# RPi-DPI-HAT_v10.net
KiCad netlist of a schematic drawn in EAGLE
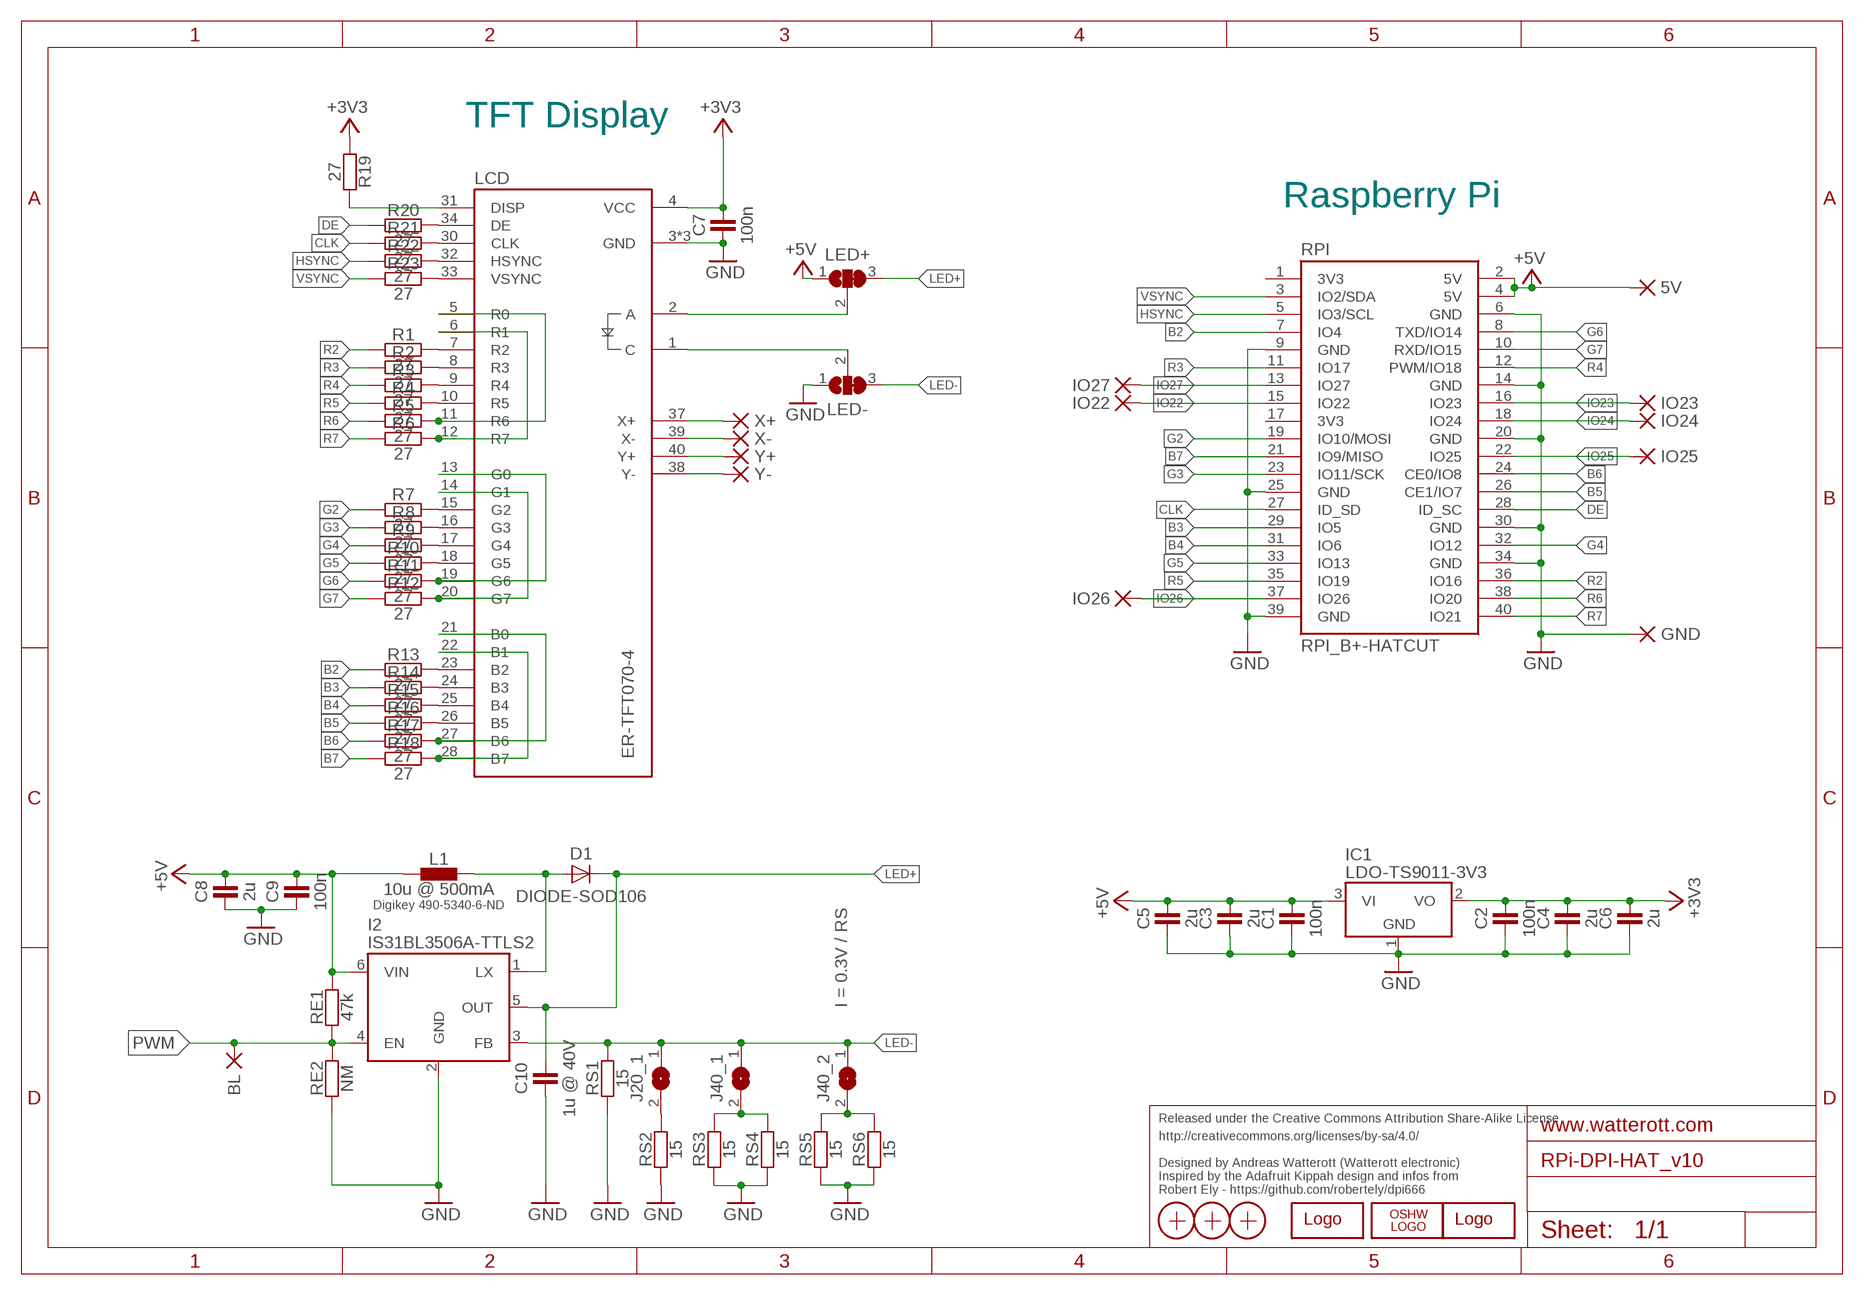
[diagram p0: schematic, sheet 1]

(export (version "E")
  (design (tool "Eeschema 10.0.6"))
  (components
    (comp (ref "5V")
      (value "PAD-0.80X1.60_NC")
      (footprint "eagle-import:PAD-0.80X1.60_NC")
      (libsource (lib "eagle-import") (part "PAD-0.80X1.60_NC"))
    )
    (comp (ref "BL")
      (value "PAD-0.80X1.60_NC")
      (footprint "eagle-import:PAD-0.80X1.60_NC")
      (libsource (lib "eagle-import") (part "PAD-0.80X1.60_NC"))
    )
    (comp (ref "C1")
      (value "100n")
      (footprint "eagle-import:C0402")
      (libsource (lib "eagle-import") (part "CAPACITOR-0402"))
    )
    (comp (ref "C2")
      (value "100n")
      (footprint "eagle-import:C0402")
      (libsource (lib "eagle-import") (part "CAPACITOR-0402"))
    )
    (comp (ref "C3")
      (value "2u")
      (footprint "eagle-import:C0402")
      (libsource (lib "eagle-import") (part "CAPACITOR-0402"))
    )
    (comp (ref "C4")
      (value "2u")
      (footprint "eagle-import:C0402")
      (libsource (lib "eagle-import") (part "CAPACITOR-0402"))
    )
    (comp (ref "C5")
      (value "2u")
      (footprint "eagle-import:C0402")
      (libsource (lib "eagle-import") (part "CAPACITOR-0402"))
    )
    (comp (ref "C6")
      (value "2u")
      (footprint "eagle-import:C0402")
      (libsource (lib "eagle-import") (part "CAPACITOR-0402"))
    )
    (comp (ref "C7")
      (value "100n")
      (footprint "eagle-import:C0402")
      (libsource (lib "eagle-import") (part "CAPACITOR-0402"))
    )
    (comp (ref "C8")
      (value "2u")
      (footprint "eagle-import:C0402")
      (libsource (lib "eagle-import") (part "CAPACITOR-0402"))
    )
    (comp (ref "C9")
      (value "100n")
      (footprint "eagle-import:C0402")
      (libsource (lib "eagle-import") (part "CAPACITOR-0402"))
    )
    (comp (ref "C10")
      (value "1u @ 40V")
      (footprint "eagle-import:C0805")
      (libsource (lib "eagle-import") (part "CAPACITOR-0805"))
    )
    (comp (ref "D1")
      (value "DIODE-SOD106")
      (footprint "eagle-import:SOD106")
      (libsource (lib "eagle-import") (part "DIODE-SOD106"))
    )
    (comp (ref "GND")
      (value "PAD-0.80X1.60_NC")
      (footprint "eagle-import:PAD-0.80X1.60_NC")
      (libsource (lib "eagle-import") (part "PAD-0.80X1.60_NC"))
    )
    (comp (ref "I2")
      (value "IS31BL3506A-TTLS2")
      (footprint "eagle-import:SOT23-6")
      (libsource (lib "eagle-import") (part "IS31BL3506A-TTLS2"))
    )
    (comp (ref "IC1")
      (value "LDO-TS9011-3V3")
      (footprint "eagle-import:SOT23")
      (libsource (lib "eagle-import") (part "LDO-TS9011-3V3"))
    )
    (comp (ref "IO22")
      (value "PAD-0.80X1.60_NC")
      (footprint "eagle-import:PAD-0.80X1.60_NC")
      (libsource (lib "eagle-import") (part "PAD-0.80X1.60_NC"))
    )
    (comp (ref "IO23")
      (value "PAD-0.80X1.60_NC")
      (footprint "eagle-import:PAD-0.80X1.60_NC")
      (libsource (lib "eagle-import") (part "PAD-0.80X1.60_NC"))
    )
    (comp (ref "IO24")
      (value "PAD-0.80X1.60_NC")
      (footprint "eagle-import:PAD-0.80X1.60_NC")
      (libsource (lib "eagle-import") (part "PAD-0.80X1.60_NC"))
    )
    (comp (ref "IO25")
      (value "PAD-0.80X1.60_NC")
      (footprint "eagle-import:PAD-0.80X1.60_NC")
      (libsource (lib "eagle-import") (part "PAD-0.80X1.60_NC"))
    )
    (comp (ref "IO26")
      (value "PAD-0.80X1.60_NC")
      (footprint "eagle-import:PAD-0.80X1.60_NC")
      (libsource (lib "eagle-import") (part "PAD-0.80X1.60_NC"))
    )
    (comp (ref "IO27")
      (value "PAD-0.80X1.60_NC")
      (footprint "eagle-import:PAD-0.80X1.60_NC")
      (libsource (lib "eagle-import") (part "PAD-0.80X1.60_NC"))
    )
    (comp (ref "J20_1")
      (value "JUMPER2-0402")
      (footprint "eagle-import:JUMPER2-0402")
      (libsource (lib "eagle-import") (part "JUMPER2-0402"))
    )
    (comp (ref "J40_1")
      (value "JUMPER2-0402")
      (footprint "eagle-import:JUMPER2-0402")
      (libsource (lib "eagle-import") (part "JUMPER2-0402"))
    )
    (comp (ref "J40_2")
      (value "JUMPER2-0402")
      (footprint "eagle-import:JUMPER2-0402")
      (libsource (lib "eagle-import") (part "JUMPER2-0402"))
    )
    (comp (ref "L1")
      (value "10u @ 500mA")
      (footprint "eagle-import:L_1212")
      (libsource (lib "eagle-import") (part "INDUCTOR-1212"))
    )
    (comp (ref "LCD")
      (value "ER-TFT070-4")
      (footprint "eagle-import:FPC40")
      (libsource (lib "eagle-import") (part "ER-TFT070-4"))
    )
    (comp (ref "LED+")
      (value "JUMPER3-0603-NC")
      (footprint "eagle-import:JUMPER3-0603_NC")
      (libsource (lib "eagle-import") (part "JUMPER3-0603-NC"))
    )
    (comp (ref "LED-")
      (value "JUMPER3-0603-NC")
      (footprint "eagle-import:JUMPER3-0603_NC")
      (libsource (lib "eagle-import") (part "JUMPER3-0603-NC"))
    )
    (comp (ref "LOGO1")
      (value "LOGO-S_PLACE_S")
      (footprint "eagle-import:SPARK_TPLACE_S")
      (libsource (lib "eagle-import") (part "LOGO-S_PLACE_S"))
    )
    (comp (ref "LOGO2")
      (value "OSHW_LOGOX0070")
      (footprint "eagle-import:OSHW_6X70")
      (libsource (lib "eagle-import") (part "OSHW_LOGOX0070"))
    )
    (comp (ref "LOGO3")
      (value "LOGO-PLACE")
      (footprint "eagle-import:LOGO_TPLACE")
      (libsource (lib "eagle-import") (part "LOGO-PLACE"))
    )
    (comp (ref "R1")
      (value "27")
      (footprint "eagle-import:C0402")
      (libsource (lib "eagle-import") (part "RESISTOR-0402"))
    )
    (comp (ref "R2")
      (value "27")
      (footprint "eagle-import:C0402")
      (libsource (lib "eagle-import") (part "RESISTOR-0402"))
    )
    (comp (ref "R3")
      (value "27")
      (footprint "eagle-import:C0402")
      (libsource (lib "eagle-import") (part "RESISTOR-0402"))
    )
    (comp (ref "R4")
      (value "27")
      (footprint "eagle-import:C0402")
      (libsource (lib "eagle-import") (part "RESISTOR-0402"))
    )
    (comp (ref "R5")
      (value "27")
      (footprint "eagle-import:C0402")
      (libsource (lib "eagle-import") (part "RESISTOR-0402"))
    )
    (comp (ref "R6")
      (value "27")
      (footprint "eagle-import:C0402")
      (libsource (lib "eagle-import") (part "RESISTOR-0402"))
    )
    (comp (ref "R7")
      (value "27")
      (footprint "eagle-import:C0402")
      (libsource (lib "eagle-import") (part "RESISTOR-0402"))
    )
    (comp (ref "R8")
      (value "27")
      (footprint "eagle-import:C0402")
      (libsource (lib "eagle-import") (part "RESISTOR-0402"))
    )
    (comp (ref "R9")
      (value "27")
      (footprint "eagle-import:C0402")
      (libsource (lib "eagle-import") (part "RESISTOR-0402"))
    )
    (comp (ref "R10")
      (value "27")
      (footprint "eagle-import:C0402")
      (libsource (lib "eagle-import") (part "RESISTOR-0402"))
    )
    (comp (ref "R11")
      (value "27")
      (footprint "eagle-import:C0402")
      (libsource (lib "eagle-import") (part "RESISTOR-0402"))
    )
    (comp (ref "R12")
      (value "27")
      (footprint "eagle-import:C0402")
      (libsource (lib "eagle-import") (part "RESISTOR-0402"))
    )
    (comp (ref "R13")
      (value "27")
      (footprint "eagle-import:C0402")
      (libsource (lib "eagle-import") (part "RESISTOR-0402"))
    )
    (comp (ref "R14")
      (value "27")
      (footprint "eagle-import:C0402")
      (libsource (lib "eagle-import") (part "RESISTOR-0402"))
    )
    (comp (ref "R15")
      (value "27")
      (footprint "eagle-import:C0402")
      (libsource (lib "eagle-import") (part "RESISTOR-0402"))
    )
    (comp (ref "R16")
      (value "27")
      (footprint "eagle-import:C0402")
      (libsource (lib "eagle-import") (part "RESISTOR-0402"))
    )
    (comp (ref "R17")
      (value "27")
      (footprint "eagle-import:C0402")
      (libsource (lib "eagle-import") (part "RESISTOR-0402"))
    )
    (comp (ref "R18")
      (value "27")
      (footprint "eagle-import:C0402")
      (libsource (lib "eagle-import") (part "RESISTOR-0402"))
    )
    (comp (ref "R19")
      (value "27")
      (footprint "eagle-import:C0402")
      (libsource (lib "eagle-import") (part "RESISTOR-0402"))
    )
    (comp (ref "R20")
      (value "27")
      (footprint "eagle-import:C0402")
      (libsource (lib "eagle-import") (part "RESISTOR-0402"))
    )
    (comp (ref "R21")
      (value "27")
      (footprint "eagle-import:C0402")
      (libsource (lib "eagle-import") (part "RESISTOR-0402"))
    )
    (comp (ref "R22")
      (value "27")
      (footprint "eagle-import:C0402")
      (libsource (lib "eagle-import") (part "RESISTOR-0402"))
    )
    (comp (ref "R23")
      (value "27")
      (footprint "eagle-import:C0402")
      (libsource (lib "eagle-import") (part "RESISTOR-0402"))
    )
    (comp (ref "RE1")
      (value "47k")
      (footprint "eagle-import:C0402")
      (libsource (lib "eagle-import") (part "RESISTOR-0402"))
    )
    (comp (ref "RE2")
      (value "NM")
      (footprint "eagle-import:C0402")
      (libsource (lib "eagle-import") (part "RESISTOR-0402"))
    )
    (comp (ref "RPI")
      (value "RPI_B+-HATCUT")
      (footprint "eagle-import:RPI-B+HAT_CUTOUT")
      (libsource (lib "eagle-import") (part "RPI_B+-HATCUT"))
    )
    (comp (ref "RS1")
      (value "15")
      (footprint "eagle-import:C0402")
      (libsource (lib "eagle-import") (part "RESISTOR-0402"))
    )
    (comp (ref "RS2")
      (value "15")
      (footprint "eagle-import:C0402")
      (libsource (lib "eagle-import") (part "RESISTOR-0402"))
    )
    (comp (ref "RS3")
      (value "15")
      (footprint "eagle-import:C0402")
      (libsource (lib "eagle-import") (part "RESISTOR-0402"))
    )
    (comp (ref "RS4")
      (value "15")
      (footprint "eagle-import:C0402")
      (libsource (lib "eagle-import") (part "RESISTOR-0402"))
    )
    (comp (ref "RS5")
      (value "15")
      (footprint "eagle-import:C0402")
      (libsource (lib "eagle-import") (part "RESISTOR-0402"))
    )
    (comp (ref "RS6")
      (value "15")
      (footprint "eagle-import:C0402")
      (libsource (lib "eagle-import") (part "RESISTOR-0402"))
    )
    (comp (ref "X+")
      (value "PAD-0.80X1.60_NC")
      (footprint "eagle-import:PAD-0.80X1.60_NC")
      (libsource (lib "eagle-import") (part "PAD-0.80X1.60_NC"))
    )
    (comp (ref "X-")
      (value "PAD-0.80X1.60_NC")
      (footprint "eagle-import:PAD-0.80X1.60_NC")
      (libsource (lib "eagle-import") (part "PAD-0.80X1.60_NC"))
    )
    (comp (ref "X1")
      (value "PASSER-07")
      (footprint "eagle-import:PASSER_07MM")
      (libsource (lib "eagle-import") (part "PASSER-07"))
    )
    (comp (ref "X2")
      (value "PASSER-07")
      (footprint "eagle-import:PASSER_07MM")
      (libsource (lib "eagle-import") (part "PASSER-07"))
    )
    (comp (ref "X3")
      (value "PASSER-07")
      (footprint "eagle-import:PASSER_07MM")
      (libsource (lib "eagle-import") (part "PASSER-07"))
    )
    (comp (ref "Y+")
      (value "PAD-0.80X1.60_NC")
      (footprint "eagle-import:PAD-0.80X1.60_NC")
      (libsource (lib "eagle-import") (part "PAD-0.80X1.60_NC"))
    )
    (comp (ref "Y-")
      (value "PAD-0.80X1.60_NC")
      (footprint "eagle-import:PAD-0.80X1.60_NC")
      (libsource (lib "eagle-import") (part "PAD-0.80X1.60_NC"))
    )
  )
  (nets
    (net (code "1") (name "+3V3") (class "Default")
      (node (ref "C2") (pin "2") (pinfunction "2_2") (pintype "passive"))
      (node (ref "C4") (pin "2") (pinfunction "2_2") (pintype "passive"))
      (node (ref "C6") (pin "2") (pinfunction "2_2") (pintype "passive"))
      (node (ref "C7") (pin "2") (pinfunction "2_2") (pintype "passive"))
      (node (ref "IC1") (pin "2") (pinfunction "VO_2") (pintype "passive"))
      (node (ref "LCD") (pin "4") (pinfunction "VCC_4") (pintype "power_in"))
      (node (ref "R19") (pin "1") (pinfunction "1_1") (pintype "passive"))
    )
    (net (code "2") (name "+5V") (class "Default")
      (node (ref "5V") (pin "1") (pinfunction "P_1") (pintype "passive"))
      (node (ref "C1") (pin "2") (pinfunction "2_2") (pintype "passive"))
      (node (ref "C3") (pin "2") (pinfunction "2_2") (pintype "passive"))
      (node (ref "C5") (pin "2") (pinfunction "2_2") (pintype "passive"))
      (node (ref "C8") (pin "2") (pinfunction "2_2") (pintype "passive"))
      (node (ref "C9") (pin "2") (pinfunction "2_2") (pintype "passive"))
      (node (ref "I2") (pin "6") (pinfunction "VIN_6") (pintype "power_in"))
      (node (ref "IC1") (pin "3") (pinfunction "VI_3") (pintype "input"))
      (node (ref "L1") (pin "1") (pinfunction "1_1") (pintype "passive"))
      (node (ref "LED+") (pin "1") (pinfunction "1_1") (pintype "passive"))
      (node (ref "RE1") (pin "2") (pinfunction "2_2") (pintype "passive"))
      (node (ref "RPI") (pin "2") (pinfunction "5V_2") (pintype "passive"))
      (node (ref "RPI") (pin "4") (pinfunction "5V_4") (pintype "passive"))
    )
    (net (code "3") (name "B2") (class "Default")
      (node (ref "R13") (pin "1") (pinfunction "1_1") (pintype "passive"))
      (node (ref "RPI") (pin "7") (pinfunction "IO4_7") (pintype "passive"))
    )
    (net (code "4") (name "B3") (class "Default")
      (node (ref "R14") (pin "1") (pinfunction "1_1") (pintype "passive"))
      (node (ref "RPI") (pin "29") (pinfunction "IO5_29") (pintype "bidirectional"))
    )
    (net (code "5") (name "B4") (class "Default")
      (node (ref "R15") (pin "1") (pinfunction "1_1") (pintype "passive"))
      (node (ref "RPI") (pin "31") (pinfunction "IO6_31") (pintype "bidirectional"))
    )
    (net (code "6") (name "B5") (class "Default")
      (node (ref "R16") (pin "1") (pinfunction "1_1") (pintype "passive"))
      (node (ref "RPI") (pin "26") (pinfunction "CE1/IO7_26") (pintype "passive"))
    )
    (net (code "7") (name "B6") (class "Default")
      (node (ref "R17") (pin "1") (pinfunction "1_1") (pintype "passive"))
      (node (ref "RPI") (pin "24") (pinfunction "CE0/IO8_24") (pintype "passive"))
    )
    (net (code "8") (name "B7") (class "Default")
      (node (ref "R18") (pin "1") (pinfunction "1_1") (pintype "passive"))
      (node (ref "RPI") (pin "21") (pinfunction "IO9/MISO_21") (pintype "passive"))
    )
    (net (code "9") (name "CLK") (class "Default")
      (node (ref "R21") (pin "1") (pinfunction "1_1") (pintype "passive"))
      (node (ref "RPI") (pin "27") (pinfunction "ID_SD_27") (pintype "bidirectional"))
    )
    (net (code "10") (name "DE") (class "Default")
      (node (ref "R20") (pin "1") (pinfunction "1_1") (pintype "passive"))
      (node (ref "RPI") (pin "28") (pinfunction "ID_SC_28") (pintype "bidirectional"))
    )
    (net (code "11") (name "G2") (class "Default")
      (node (ref "R7") (pin "1") (pinfunction "1_1") (pintype "passive"))
      (node (ref "RPI") (pin "19") (pinfunction "IO10/MOSI_19") (pintype "passive"))
    )
    (net (code "12") (name "G3") (class "Default")
      (node (ref "R8") (pin "1") (pinfunction "1_1") (pintype "passive"))
      (node (ref "RPI") (pin "23") (pinfunction "IO11/SCK_23") (pintype "passive"))
    )
    (net (code "13") (name "G4") (class "Default")
      (node (ref "R9") (pin "1") (pinfunction "1_1") (pintype "passive"))
      (node (ref "RPI") (pin "32") (pinfunction "IO12_32") (pintype "bidirectional"))
    )
    (net (code "14") (name "G5") (class "Default")
      (node (ref "R10") (pin "1") (pinfunction "1_1") (pintype "passive"))
      (node (ref "RPI") (pin "33") (pinfunction "IO13_33") (pintype "bidirectional"))
    )
    (net (code "15") (name "G6") (class "Default")
      (node (ref "R11") (pin "1") (pinfunction "1_1") (pintype "passive"))
      (node (ref "RPI") (pin "8") (pinfunction "TXD/IO14_8") (pintype "passive"))
    )
    (net (code "16") (name "G7") (class "Default")
      (node (ref "R12") (pin "1") (pinfunction "1_1") (pintype "passive"))
      (node (ref "RPI") (pin "10") (pinfunction "RXD/IO15_10") (pintype "passive"))
    )
    (net (code "17") (name "GND") (class "Default")
      (node (ref "C1") (pin "1") (pinfunction "1_1") (pintype "passive"))
      (node (ref "C10") (pin "1") (pinfunction "1_1") (pintype "passive"))
      (node (ref "C2") (pin "1") (pinfunction "1_1") (pintype "passive"))
      (node (ref "C3") (pin "1") (pinfunction "1_1") (pintype "passive"))
      (node (ref "C4") (pin "1") (pinfunction "1_1") (pintype "passive"))
      (node (ref "C5") (pin "1") (pinfunction "1_1") (pintype "passive"))
      (node (ref "C6") (pin "1") (pinfunction "1_1") (pintype "passive"))
      (node (ref "C7") (pin "1") (pinfunction "1_1") (pintype "passive"))
      (node (ref "C8") (pin "1") (pinfunction "1_1") (pintype "passive"))
      (node (ref "C9") (pin "1") (pinfunction "1_1") (pintype "passive"))
      (node (ref "GND") (pin "1") (pinfunction "P_1") (pintype "passive"))
      (node (ref "I2") (pin "2") (pinfunction "GND_2") (pintype "power_in"))
      (node (ref "IC1") (pin "1") (pinfunction "GND_1") (pintype "passive"))
      (node (ref "LCD") (pin "29") (pinfunction "GND_29") (pintype "power_in"))
      (node (ref "LCD") (pin "3") (pinfunction "GND_3") (pintype "power_in"))
      (node (ref "LCD") (pin "36") (pinfunction "GND_36") (pintype "power_in"))
      (node (ref "LED-") (pin "1") (pinfunction "1_1") (pintype "passive"))
      (node (ref "RE2") (pin "1") (pinfunction "1_1") (pintype "passive"))
      (node (ref "RPI") (pin "14") (pinfunction "GND_14") (pintype "passive"))
      (node (ref "RPI") (pin "20") (pinfunction "GND_20") (pintype "passive"))
      (node (ref "RPI") (pin "25") (pinfunction "GND_25") (pintype "passive"))
      (node (ref "RPI") (pin "30") (pinfunction "GND_30") (pintype "bidirectional"))
      (node (ref "RPI") (pin "34") (pinfunction "GND_34") (pintype "bidirectional"))
      (node (ref "RPI") (pin "39") (pinfunction "GND_39") (pintype "bidirectional"))
      (node (ref "RPI") (pin "6") (pinfunction "GND_6") (pintype "passive"))
      (node (ref "RPI") (pin "9") (pinfunction "GND_9") (pintype "passive"))
      (node (ref "RS1") (pin "1") (pinfunction "1_1") (pintype "passive"))
      (node (ref "RS2") (pin "1") (pinfunction "1_1") (pintype "passive"))
      (node (ref "RS3") (pin "1") (pinfunction "1_1") (pintype "passive"))
      (node (ref "RS4") (pin "1") (pinfunction "1_1") (pintype "passive"))
      (node (ref "RS5") (pin "1") (pinfunction "1_1") (pintype "passive"))
      (node (ref "RS6") (pin "1") (pinfunction "1_1") (pintype "passive"))
    )
    (net (code "18") (name "HSYNC") (class "Default")
      (node (ref "R22") (pin "1") (pinfunction "1_1") (pintype "passive"))
      (node (ref "RPI") (pin "5") (pinfunction "IO3/SCL_5") (pintype "passive"))
    )
    (net (code "19") (name "IO22") (class "Default")
      (node (ref "IO22") (pin "1") (pinfunction "P_1") (pintype "passive"))
      (node (ref "RPI") (pin "15") (pinfunction "IO22_15") (pintype "passive"))
    )
    (net (code "20") (name "IO23") (class "Default")
      (node (ref "IO23") (pin "1") (pinfunction "P_1") (pintype "passive"))
      (node (ref "RPI") (pin "16") (pinfunction "IO23_16") (pintype "passive"))
    )
    (net (code "21") (name "IO24") (class "Default")
      (node (ref "IO24") (pin "1") (pinfunction "P_1") (pintype "passive"))
      (node (ref "RPI") (pin "18") (pinfunction "IO24_18") (pintype "passive"))
    )
    (net (code "22") (name "IO25") (class "Default")
      (node (ref "IO25") (pin "1") (pinfunction "P_1") (pintype "passive"))
      (node (ref "RPI") (pin "22") (pinfunction "IO25_22") (pintype "passive"))
    )
    (net (code "23") (name "IO26") (class "Default")
      (node (ref "IO26") (pin "1") (pinfunction "P_1") (pintype "passive"))
      (node (ref "RPI") (pin "37") (pinfunction "IO26_37") (pintype "bidirectional"))
    )
    (net (code "24") (name "IO27") (class "Default")
      (node (ref "IO27") (pin "1") (pinfunction "P_1") (pintype "passive"))
      (node (ref "RPI") (pin "13") (pinfunction "IO27_13") (pintype "passive"))
    )
    (net (code "25") (name "LED+") (class "Default")
      (node (ref "C10") (pin "2") (pinfunction "2_2") (pintype "passive"))
      (node (ref "D1") (pin "C") (pinfunction "C_C") (pintype "passive"))
      (node (ref "I2") (pin "5") (pinfunction "OUT_5") (pintype "power_in"))
      (node (ref "LED+") (pin "3") (pinfunction "3_3") (pintype "passive"))
    )
    (net (code "26") (name "LED-") (class "Default")
      (node (ref "I2") (pin "3") (pinfunction "FB_3") (pintype "input"))
      (node (ref "J20_1") (pin "1") (pinfunction "1_1") (pintype "passive"))
      (node (ref "J40_1") (pin "1") (pinfunction "1_1") (pintype "passive"))
      (node (ref "J40_2") (pin "1") (pinfunction "1_1") (pintype "passive"))
      (node (ref "LED-") (pin "3") (pinfunction "3_3") (pintype "passive"))
      (node (ref "RS1") (pin "2") (pinfunction "2_2") (pintype "passive"))
    )
    (net (code "27") (name "Net-(I2-LX)") (class "Default")
      (node (ref "D1") (pin "A") (pinfunction "A_A") (pintype "passive"))
      (node (ref "I2") (pin "1") (pinfunction "LX_1") (pintype "power_in"))
      (node (ref "L1") (pin "2") (pinfunction "2_2") (pintype "passive"))
    )
    (net (code "28") (name "Net-(J20_1-Pad2)") (class "Default")
      (node (ref "J20_1") (pin "2") (pinfunction "2_2") (pintype "passive"))
      (node (ref "RS2") (pin "2") (pinfunction "2_2") (pintype "passive"))
    )
    (net (code "29") (name "Net-(J40_1-Pad2)") (class "Default")
      (node (ref "J40_1") (pin "2") (pinfunction "2_2") (pintype "passive"))
      (node (ref "RS3") (pin "2") (pinfunction "2_2") (pintype "passive"))
      (node (ref "RS4") (pin "2") (pinfunction "2_2") (pintype "passive"))
    )
    (net (code "30") (name "Net-(J40_2-Pad2)") (class "Default")
      (node (ref "J40_2") (pin "2") (pinfunction "2_2") (pintype "passive"))
      (node (ref "RS5") (pin "2") (pinfunction "2_2") (pintype "passive"))
      (node (ref "RS6") (pin "2") (pinfunction "2_2") (pintype "passive"))
    )
    (net (code "31") (name "Net-(LCD-A)") (class "Default")
      (node (ref "LCD") (pin "2") (pinfunction "A_2") (pintype "power_in"))
      (node (ref "LED+") (pin "2") (pinfunction "2_2") (pintype "passive"))
    )
    (net (code "32") (name "Net-(LCD-B0)") (class "Default")
      (node (ref "LCD") (pin "21") (pinfunction "B0_21") (pintype "input"))
      (node (ref "LCD") (pin "27") (pinfunction "B6_27") (pintype "input"))
      (node (ref "R17") (pin "2") (pinfunction "2_2") (pintype "passive"))
    )
    (net (code "33") (name "Net-(LCD-B1)") (class "Default")
      (node (ref "LCD") (pin "22") (pinfunction "B1_22") (pintype "input"))
      (node (ref "LCD") (pin "28") (pinfunction "B7_28") (pintype "input"))
      (node (ref "R18") (pin "2") (pinfunction "2_2") (pintype "passive"))
    )
    (net (code "34") (name "Net-(LCD-B2)") (class "Default")
      (node (ref "LCD") (pin "23") (pinfunction "B2_23") (pintype "input"))
      (node (ref "R13") (pin "2") (pinfunction "2_2") (pintype "passive"))
    )
    (net (code "35") (name "Net-(LCD-B3)") (class "Default")
      (node (ref "LCD") (pin "24") (pinfunction "B3_24") (pintype "input"))
      (node (ref "R14") (pin "2") (pinfunction "2_2") (pintype "passive"))
    )
    (net (code "36") (name "Net-(LCD-B4)") (class "Default")
      (node (ref "LCD") (pin "25") (pinfunction "B4_25") (pintype "input"))
      (node (ref "R15") (pin "2") (pinfunction "2_2") (pintype "passive"))
    )
    (net (code "37") (name "Net-(LCD-B5)") (class "Default")
      (node (ref "LCD") (pin "26") (pinfunction "B5_26") (pintype "input"))
      (node (ref "R16") (pin "2") (pinfunction "2_2") (pintype "passive"))
    )
    (net (code "38") (name "Net-(LCD-C)") (class "Default")
      (node (ref "LCD") (pin "1") (pinfunction "C_1") (pintype "power_in"))
      (node (ref "LED-") (pin "2") (pinfunction "2_2") (pintype "passive"))
    )
    (net (code "39") (name "Net-(LCD-CLK)") (class "Default")
      (node (ref "LCD") (pin "30") (pinfunction "CLK_30") (pintype "input"))
      (node (ref "R21") (pin "2") (pinfunction "2_2") (pintype "passive"))
    )
    (net (code "40") (name "Net-(LCD-DE)") (class "Default")
      (node (ref "LCD") (pin "34") (pinfunction "DE_34") (pintype "input"))
      (node (ref "R20") (pin "2") (pinfunction "2_2") (pintype "passive"))
    )
    (net (code "41") (name "Net-(LCD-DISP)") (class "Default")
      (node (ref "LCD") (pin "31") (pinfunction "DISP_31") (pintype "input"))
      (node (ref "R19") (pin "2") (pinfunction "2_2") (pintype "passive"))
    )
    (net (code "42") (name "Net-(LCD-G0)") (class "Default")
      (node (ref "LCD") (pin "13") (pinfunction "G0_13") (pintype "input"))
      (node (ref "LCD") (pin "19") (pinfunction "G6_19") (pintype "input"))
      (node (ref "R11") (pin "2") (pinfunction "2_2") (pintype "passive"))
    )
    (net (code "43") (name "Net-(LCD-G1)") (class "Default")
      (node (ref "LCD") (pin "14") (pinfunction "G1_14") (pintype "input"))
      (node (ref "LCD") (pin "20") (pinfunction "G7_20") (pintype "input"))
      (node (ref "R12") (pin "2") (pinfunction "2_2") (pintype "passive"))
    )
    (net (code "44") (name "Net-(LCD-G2)") (class "Default")
      (node (ref "LCD") (pin "15") (pinfunction "G2_15") (pintype "input"))
      (node (ref "R7") (pin "2") (pinfunction "2_2") (pintype "passive"))
    )
    (net (code "45") (name "Net-(LCD-G3)") (class "Default")
      (node (ref "LCD") (pin "16") (pinfunction "G3_16") (pintype "input"))
      (node (ref "R8") (pin "2") (pinfunction "2_2") (pintype "passive"))
    )
    (net (code "46") (name "Net-(LCD-G4)") (class "Default")
      (node (ref "LCD") (pin "17") (pinfunction "G4_17") (pintype "input"))
      (node (ref "R9") (pin "2") (pinfunction "2_2") (pintype "passive"))
    )
    (net (code "47") (name "Net-(LCD-G5)") (class "Default")
      (node (ref "LCD") (pin "18") (pinfunction "G5_18") (pintype "input"))
      (node (ref "R10") (pin "2") (pinfunction "2_2") (pintype "passive"))
    )
    (net (code "48") (name "Net-(LCD-HSYNC)") (class "Default")
      (node (ref "LCD") (pin "32") (pinfunction "HSYNC_32") (pintype "input"))
      (node (ref "R22") (pin "2") (pinfunction "2_2") (pintype "passive"))
    )
    (net (code "49") (name "Net-(LCD-R0)") (class "Default")
      (node (ref "LCD") (pin "11") (pinfunction "R6_11") (pintype "input"))
      (node (ref "LCD") (pin "5") (pinfunction "R0_5") (pintype "input"))
      (node (ref "R5") (pin "2") (pinfunction "2_2") (pintype "passive"))
    )
    (net (code "50") (name "Net-(LCD-R1)") (class "Default")
      (node (ref "LCD") (pin "12") (pinfunction "R7_12") (pintype "input"))
      (node (ref "LCD") (pin "6") (pinfunction "R1_6") (pintype "input"))
      (node (ref "R6") (pin "2") (pinfunction "2_2") (pintype "passive"))
    )
    (net (code "51") (name "Net-(LCD-R2)") (class "Default")
      (node (ref "LCD") (pin "7") (pinfunction "R2_7") (pintype "input"))
      (node (ref "R1") (pin "2") (pinfunction "2_2") (pintype "passive"))
    )
    (net (code "52") (name "Net-(LCD-R3)") (class "Default")
      (node (ref "LCD") (pin "8") (pinfunction "R3_8") (pintype "input"))
      (node (ref "R2") (pin "2") (pinfunction "2_2") (pintype "passive"))
    )
    (net (code "53") (name "Net-(LCD-R4)") (class "Default")
      (node (ref "LCD") (pin "9") (pinfunction "R4_9") (pintype "input"))
      (node (ref "R3") (pin "2") (pinfunction "2_2") (pintype "passive"))
    )
    (net (code "54") (name "Net-(LCD-R5)") (class "Default")
      (node (ref "LCD") (pin "10") (pinfunction "R5_10") (pintype "input"))
      (node (ref "R4") (pin "2") (pinfunction "2_2") (pintype "passive"))
    )
    (net (code "55") (name "Net-(LCD-VSYNC)") (class "Default")
      (node (ref "LCD") (pin "33") (pinfunction "VSYNC_33") (pintype "input"))
      (node (ref "R23") (pin "2") (pinfunction "2_2") (pintype "passive"))
    )
    (net (code "56") (name "Net-(LCD-X+)") (class "Default")
      (node (ref "LCD") (pin "37") (pinfunction "X+_37") (pintype "passive"))
      (node (ref "X+") (pin "1") (pinfunction "P_1") (pintype "passive"))
    )
    (net (code "57") (name "Net-(LCD-X-)") (class "Default")
      (node (ref "LCD") (pin "39") (pinfunction "X-_39") (pintype "passive"))
      (node (ref "X-") (pin "1") (pinfunction "P_1") (pintype "passive"))
    )
    (net (code "58") (name "Net-(LCD-Y+)") (class "Default")
      (node (ref "LCD") (pin "40") (pinfunction "Y+_40") (pintype "passive"))
      (node (ref "Y+") (pin "1") (pinfunction "P_1") (pintype "passive"))
    )
    (net (code "59") (name "Net-(LCD-Y-)") (class "Default")
      (node (ref "LCD") (pin "38") (pinfunction "Y-_38") (pintype "passive"))
      (node (ref "Y-") (pin "1") (pinfunction "P_1") (pintype "passive"))
    )
    (net (code "60") (name "PWM") (class "Default")
      (node (ref "BL") (pin "1") (pinfunction "P_1") (pintype "passive"))
      (node (ref "I2") (pin "4") (pinfunction "EN_4") (pintype "input"))
      (node (ref "RE1") (pin "1") (pinfunction "1_1") (pintype "passive"))
      (node (ref "RE2") (pin "2") (pinfunction "2_2") (pintype "passive"))
    )
    (net (code "61") (name "R2") (class "Default")
      (node (ref "R1") (pin "1") (pinfunction "1_1") (pintype "passive"))
      (node (ref "RPI") (pin "36") (pinfunction "IO16_36") (pintype "bidirectional"))
    )
    (net (code "62") (name "R3") (class "Default")
      (node (ref "R2") (pin "1") (pinfunction "1_1") (pintype "passive"))
      (node (ref "RPI") (pin "11") (pinfunction "IO17_11") (pintype "passive"))
    )
    (net (code "63") (name "R4") (class "Default")
      (node (ref "R3") (pin "1") (pinfunction "1_1") (pintype "passive"))
      (node (ref "RPI") (pin "12") (pinfunction "PWM/IO18_12") (pintype "passive"))
    )
    (net (code "64") (name "R5") (class "Default")
      (node (ref "R4") (pin "1") (pinfunction "1_1") (pintype "passive"))
      (node (ref "RPI") (pin "35") (pinfunction "IO19_35") (pintype "bidirectional"))
    )
    (net (code "65") (name "R6") (class "Default")
      (node (ref "R5") (pin "1") (pinfunction "1_1") (pintype "passive"))
      (node (ref "RPI") (pin "38") (pinfunction "IO20_38") (pintype "bidirectional"))
    )
    (net (code "66") (name "R7") (class "Default")
      (node (ref "R6") (pin "1") (pinfunction "1_1") (pintype "passive"))
      (node (ref "RPI") (pin "40") (pinfunction "IO21_40") (pintype "bidirectional"))
    )
    (net (code "67") (name "VSYNC") (class "Default")
      (node (ref "R23") (pin "1") (pinfunction "1_1") (pintype "passive"))
      (node (ref "RPI") (pin "3") (pinfunction "IO2/SDA_3") (pintype "passive"))
    )
    (net (code "68") (name "unconnected-(RPI-3V3-Pad1)") (class "Default")
      (node (ref "RPI") (pin "1") (pinfunction "3V3_1") (pintype "passive"))
    )
    (net (code "69") (name "unconnected-(RPI-3V3-Pad17)") (class "Default")
      (node (ref "RPI") (pin "17") (pinfunction "3V3_17") (pintype "passive"))
    )
  )
)
